# MCU.net
KiCad netlist of a schematic drawn in Altium Designer
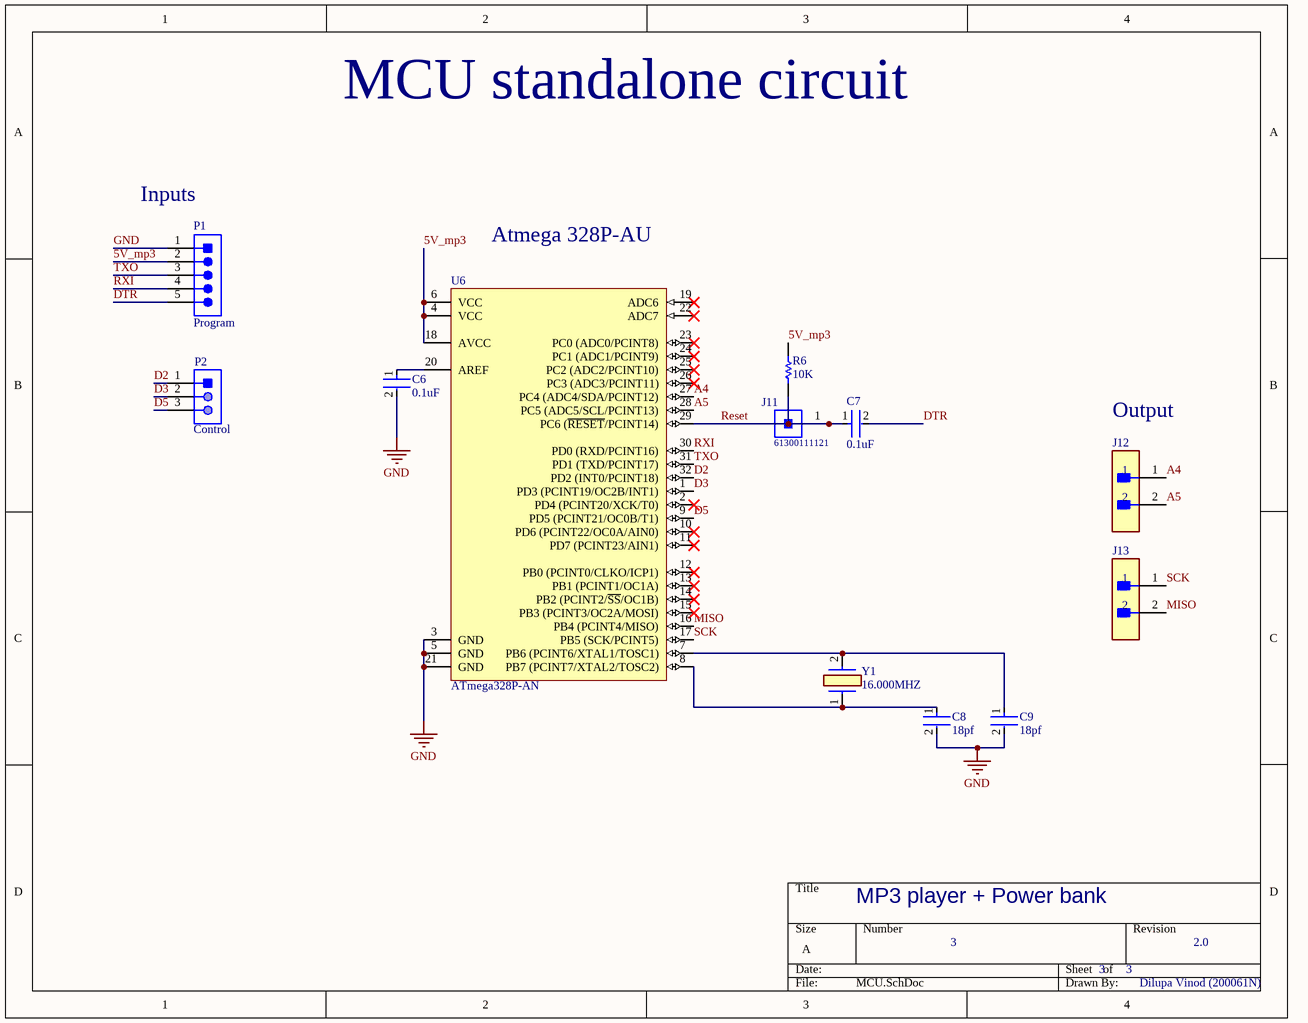
[diagram p0: MCU.SchDoc]

(export (version "E")
  (design (tool "Eeschema 10.0.6"))
  (components
    (comp (ref "C6")
      (value "0.1uF")
      (footprint "FP-GRM21B-0_15-MFG")
      (description "Chip Multilayer Ceramic Capacitors for General Purpose, 0805, 22uF, X5R, 15%, 20%, 6.3V")
      (fields (field (name "VOLTAGE") "6.3V") (field (name "TOLERANCE") "20%"))
      (libsource (lib "Altium Content Vault") (part "b4654b650e69147ec39a6b967a45e02"))
    )
    (comp (ref "C7")
      (value "0.1uF")
      (footprint "FP-GRM21B-0_15-MFG")
      (description "Chip Multilayer Ceramic Capacitors for General Purpose, 0805, 22uF, X5R, 15%, 20%, 6.3V")
      (fields (field (name "VOLTAGE") "6.3V") (field (name "TOLERANCE") "20%"))
      (libsource (lib "Altium Content Vault") (part "b4654b650e69147ec39a6b967a45e02"))
    )
    (comp (ref "C8")
      (value "18pf")
      (footprint "FP-GRM21B-0_15-MFG")
      (description "Chip Multilayer Ceramic Capacitors for General Purpose, 0805, 22uF, X5R, 15%, 20%, 6.3V")
      (fields (field (name "VOLTAGE") "6.3V") (field (name "TOLERANCE") "20%"))
      (libsource (lib "Altium Content Vault") (part "b4654b650e69147ec39a6b967a45e02"))
    )
    (comp (ref "C9")
      (value "18pf")
      (footprint "FP-GRM21B-0_15-MFG")
      (description "Chip Multilayer Ceramic Capacitors for General Purpose, 0805, 22uF, X5R, 15%, 20%, 6.3V")
      (fields (field (name "VOLTAGE") "6.3V") (field (name "TOLERANCE") "20%"))
      (libsource (lib "Altium Content Vault") (part "b4654b650e69147ec39a6b967a45e02"))
    )
    (comp (ref "J11")
      (value "61300111121")
      (footprint "61300111121")
      (description "THT Vertical Pin Header WR-PHD, Pitch 2.54 mm, Single Row, 1 pins")
      (fields
        (field (name "MANUFACTURER") "Wurth Elektronik")
        (field (name "MANUFACTURER_1") "Wurth Electronics")
        (field (name "PUBLISHER") "WurthElektronik")
      )
      (libsource (lib "MP3_Power_bank") (part "CMP-1502-01058-1"))
    )
    (comp (ref "J12")
      (value "Mp3_p")
      (footprint "FP-M22-2510205-MFG")
      (description "CONN HEADER VERT 2POS 2MM")
      (fields
        (field (name "MANUFACTURER") "Harwin")
        (field (name "OCTOPART") "https://octopart.com/m22-2510205-harwin-2538221")
      )
      (libsource (lib "Altium Content Vault") (part "3bc925449376181038e59eaffc5286c"))
    )
    (comp (ref "J13")
      (value "Mp3_p")
      (footprint "FP-M22-2510205-MFG")
      (description "CONN HEADER VERT 2POS 2MM")
      (fields
        (field (name "MANUFACTURER") "Harwin")
        (field (name "OCTOPART") "https://octopart.com/m22-2510205-harwin-2538221")
      )
      (libsource (lib "Altium Content Vault") (part "3bc925449376181038e59eaffc5286c"))
    )
    (comp (ref "P1")
      (value "Program")
      (footprint "TECO-640456-5")
      (fields (field (name "MANUFACTURER") "TE Connectivity"))
      (libsource (lib "Altium Content Vault") (part "CN-1P-M-R5"))
    )
    (comp (ref "P2")
      (value "Control")
      (footprint "MOLX-22-28-4033_V")
      (description "Male Header, Pitch 2.54 mm, 1 x 3 Position, Height 8.38 mm, Tail Length 3.18 mm, RoHS, Bulk")
      (fields (field (name "MANUFACTURER") "Molex"))
      (libsource (lib "Altium Content Vault") (part "CN-1P-M-R3"))
    )
    (comp (ref "R6")
      (value "10K")
      (footprint "RESC2013X50X30LL20T20")
      (fields (field (name "MANUFACTURER") "Vishay Dale") (field (name "PART NUMBER") "CRCW08050000Z0EA"))
      (libsource (lib "Altium Content Vault") (part "RES"))
    )
    (comp (ref "U6")
      (value "ATmega328P-AN")
      (footprint "32A_N")
      (libsource (lib "Altium Content Vault") (part "MC-8B-ATM48-SQ32"))
    )
    (comp (ref "Y1")
      (value "16.000MHZ")
      (footprint "SamacSys:ABLS")
      (description "Crystal or Oscillator")
      (fields
        (field (name "MANUFACTURER_PART_NUMBER") "ABLS-16.000MHZ-B4-T")
        (field (name "MOUSER PART NUMBER") "815-ABLS-16.0M-T")
      )
      (libsource (lib "*") (part "ABLS-16.000MHZ-B4-T"))
    )
  )
  (nets
    (net (code "1") (name "/5V_mp3") (class "Default")
      (node (ref "P1") (pin "2") (pinfunction "RXI_2") (pintype "passive"))
      (node (ref "R6") (pin "2") (pinfunction "2_2") (pintype "passive"))
      (node (ref "U6") (pin "18") (pinfunction "AVCC_18") (pintype "power_in"))
      (node (ref "U6") (pin "4") (pinfunction "VCC_4") (pintype "power_in"))
      (node (ref "U6") (pin "6") (pinfunction "VCC_6") (pintype "power_in"))
    )
    (net (code "2") (name "/A4") (class "Default")
      (node (ref "J12") (pin "1") (pinfunction "1_1") (pintype "passive"))
      (node (ref "U6") (pin "27") (pinfunction "PC4_(ADC4/SDA/PCINT12)_27") (pintype "bidirectional"))
    )
    (net (code "3") (name "/A5") (class "Default")
      (node (ref "J12") (pin "2") (pinfunction "2_2") (pintype "passive"))
      (node (ref "U6") (pin "28") (pinfunction "PC5_(ADC5/SCL/PCINT13)_28") (pintype "bidirectional"))
    )
    (net (code "4") (name "/D2") (class "Default")
      (node (ref "P2") (pin "1") (pinfunction "1_1") (pintype "passive"))
      (node (ref "U6") (pin "32") (pinfunction "PD2_(INT0/PCINT18)_32") (pintype "bidirectional"))
    )
    (net (code "5") (name "/D3") (class "Default")
      (node (ref "P2") (pin "2") (pinfunction "2_2") (pintype "passive"))
      (node (ref "U6") (pin "1") (pinfunction "PD3_(PCINT19/OC2B/INT1)_1") (pintype "bidirectional"))
    )
    (net (code "6") (name "/D5") (class "Default")
      (node (ref "P2") (pin "3") (pinfunction "3_3") (pintype "passive"))
      (node (ref "U6") (pin "9") (pinfunction "PD5_(PCINT21/OC0B/T1)_9") (pintype "bidirectional"))
    )
    (net (code "7") (name "/DTR") (class "Default")
      (node (ref "C7") (pin "2") (pinfunction "2_2") (pintype "passive"))
      (node (ref "P1") (pin "5") (pinfunction "CTS_5") (pintype "passive"))
    )
    (net (code "8") (name "/MISO") (class "Default")
      (node (ref "J13") (pin "2") (pinfunction "2_2") (pintype "passive"))
      (node (ref "U6") (pin "16") (pinfunction "PB4_(PCINT4/MISO)_16") (pintype "bidirectional"))
    )
    (net (code "9") (name "/RXI") (class "Default")
      (node (ref "P1") (pin "4") (pinfunction "VCC_4") (pintype "passive"))
      (node (ref "U6") (pin "30") (pinfunction "PD0_(RXD/PCINT16)_30") (pintype "bidirectional"))
    )
    (net (code "10") (name "/Reset") (class "Default")
      (node (ref "C7") (pin "1") (pinfunction "1_1") (pintype "passive"))
      (node (ref "J11") (pin "1") (pinfunction "1_1") (pintype "passive"))
      (node (ref "R6") (pin "1") (pinfunction "1_1") (pintype "passive"))
      (node (ref "U6") (pin "29") (pinfunction "PC6_(~{RESET}/PCINT14)_29") (pintype "bidirectional"))
    )
    (net (code "11") (name "/SCK") (class "Default")
      (node (ref "J13") (pin "1") (pinfunction "1_1") (pintype "passive"))
      (node (ref "U6") (pin "17") (pinfunction "PB5_(SCK/PCINT5)_17") (pintype "bidirectional"))
    )
    (net (code "12") (name "/TXO") (class "Default")
      (node (ref "P1") (pin "3") (pinfunction "TXO_3") (pintype "passive"))
      (node (ref "U6") (pin "31") (pinfunction "PD1_(TXD/PCINT17)_31") (pintype "bidirectional"))
    )
    (net (code "13") (name "GND") (class "Default")
      (node (ref "C6") (pin "2") (pinfunction "2_2") (pintype "passive"))
      (node (ref "C8") (pin "2") (pinfunction "2_2") (pintype "passive"))
      (node (ref "C9") (pin "2") (pinfunction "2_2") (pintype "passive"))
      (node (ref "P1") (pin "1") (pinfunction "DTR_1") (pintype "passive"))
      (node (ref "U6") (pin "21") (pinfunction "GND_21") (pintype "power_in"))
      (node (ref "U6") (pin "3") (pinfunction "GND_3") (pintype "power_in"))
      (node (ref "U6") (pin "5") (pinfunction "GND_5") (pintype "power_in"))
    )
    (net (code "14") (name "Net-(U6-AREF)") (class "Default")
      (node (ref "C6") (pin "1") (pinfunction "1_1") (pintype "passive"))
      (node (ref "U6") (pin "20") (pinfunction "AREF_20") (pintype "passive"))
    )
    (net (code "15") (name "Net-(U6-PB6_(PCINT6{slash}XTAL1{slash}TOSC1))") (class "Default")
      (node (ref "C9") (pin "1") (pinfunction "1_1") (pintype "passive"))
      (node (ref "U6") (pin "7") (pinfunction "PB6_(PCINT6/XTAL1/TOSC1)_7") (pintype "bidirectional"))
      (node (ref "Y1") (pin "2") (pinfunction "2_2") (pintype "passive"))
    )
    (net (code "16") (name "Net-(U6-PB7_(PCINT7{slash}XTAL2{slash}TOSC2))") (class "Default")
      (node (ref "C8") (pin "1") (pinfunction "1_1") (pintype "passive"))
      (node (ref "U6") (pin "8") (pinfunction "PB7_(PCINT7/XTAL2/TOSC2)_8") (pintype "bidirectional"))
      (node (ref "Y1") (pin "1") (pinfunction "1_1") (pintype "passive"))
    )
    (net (code "17") (name "unconnected-(U6-ADC6-Pad19)") (class "Default")
      (node (ref "U6") (pin "19") (pinfunction "ADC6_19") (pintype "input+no_connect"))
    )
    (net (code "18") (name "unconnected-(U6-ADC7-Pad22)") (class "Default")
      (node (ref "U6") (pin "22") (pinfunction "ADC7_22") (pintype "input+no_connect"))
    )
    (net (code "19") (name "unconnected-(U6-PB0_(PCINT0{slash}CLKO{slash}ICP1)-Pad12)") (class "Default")
      (node (ref "U6") (pin "12") (pinfunction "PB0_(PCINT0/CLKO/ICP1)_12") (pintype "bidirectional+no_connect"))
    )
    (net (code "20") (name "unconnected-(U6-PB1_(PCINT1{slash}OC1A)-Pad13)") (class "Default")
      (node (ref "U6") (pin "13") (pinfunction "PB1_(PCINT1/OC1A)_13") (pintype "bidirectional+no_connect"))
    )
    (net (code "21") (name "unconnected-(U6-PB2_(PCINT2{slash}~{SS}{slash}OC1B)-Pad14)") (class "Default")
      (node (ref "U6") (pin "14") (pinfunction "PB2_(PCINT2/~{SS}/OC1B)_14") (pintype "bidirectional+no_connect"))
    )
    (net (code "22") (name "unconnected-(U6-PB3_(PCINT3{slash}OC2A{slash}MOSI)-Pad15)") (class "Default")
      (node (ref "U6") (pin "15") (pinfunction "PB3_(PCINT3/OC2A/MOSI)_15") (pintype "bidirectional+no_connect"))
    )
    (net (code "23") (name "unconnected-(U6-PC0_(ADC0{slash}PCINT8)-Pad23)") (class "Default")
      (node (ref "U6") (pin "23") (pinfunction "PC0_(ADC0/PCINT8)_23") (pintype "bidirectional+no_connect"))
    )
    (net (code "24") (name "unconnected-(U6-PC1_(ADC1{slash}PCINT9)-Pad24)") (class "Default")
      (node (ref "U6") (pin "24") (pinfunction "PC1_(ADC1/PCINT9)_24") (pintype "bidirectional+no_connect"))
    )
    (net (code "25") (name "unconnected-(U6-PC2_(ADC2{slash}PCINT10)-Pad25)") (class "Default")
      (node (ref "U6") (pin "25") (pinfunction "PC2_(ADC2/PCINT10)_25") (pintype "bidirectional+no_connect"))
    )
    (net (code "26") (name "unconnected-(U6-PC3_(ADC3{slash}PCINT11)-Pad26)") (class "Default")
      (node (ref "U6") (pin "26") (pinfunction "PC3_(ADC3/PCINT11)_26") (pintype "bidirectional+no_connect"))
    )
    (net (code "27") (name "unconnected-(U6-PD4_(PCINT20{slash}XCK{slash}T0)-Pad2)") (class "Default")
      (node (ref "U6") (pin "2") (pinfunction "PD4_(PCINT20/XCK/T0)_2") (pintype "bidirectional+no_connect"))
    )
    (net (code "28") (name "unconnected-(U6-PD6_(PCINT22{slash}OC0A{slash}AIN0)-Pad10)") (class "Default")
      (node (ref "U6") (pin "10") (pinfunction "PD6_(PCINT22/OC0A/AIN0)_10") (pintype "bidirectional+no_connect"))
    )
    (net (code "29") (name "unconnected-(U6-PD7_(PCINT23{slash}AIN1)-Pad11)") (class "Default")
      (node (ref "U6") (pin "11") (pinfunction "PD7_(PCINT23/AIN1)_11") (pintype "bidirectional+no_connect"))
    )
  )
)
